# rail_safety.net
KiCad netlist of a schematic drawn in Altium Designer
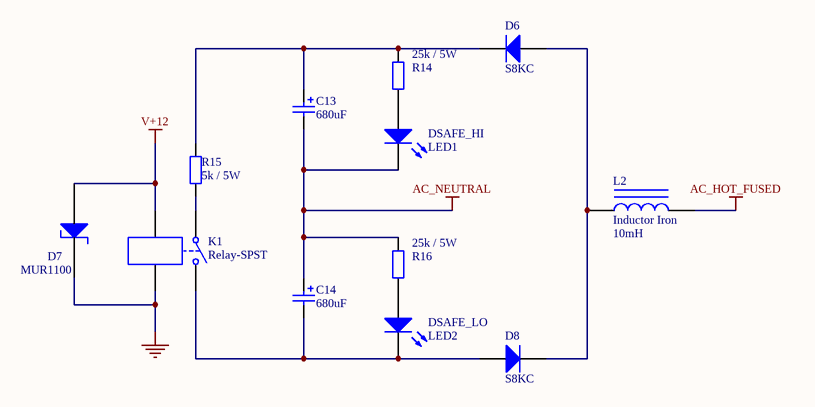
[diagram p0: rail_safety.SchDoc]

(export (version "E")
  (design (tool "Eeschema 10.0.6"))
  (components
    (comp (ref "C13")
      (value "680uF")
      (footprint "Cap_450v_680uF")
      (description "Polarized Capacitor (Surface Mount)")
      (fields (field (name "Comment") "Cap Pol3") (field (name "PUBLISHER") "Altium Limited"))
      (libsource (lib "Miscellaneous Devices") (part "Cap Pol3"))
    )
    (comp (ref "C14")
      (value "680uF")
      (footprint "Cap_450v_680uF")
      (description "Polarized Capacitor (Surface Mount)")
      (fields (field (name "Comment") "Cap Pol3") (field (name "PUBLISHER") "Altium Limited"))
      (libsource (lib "Miscellaneous Devices") (part "Cap Pol3"))
    )
    (comp (ref "D6")
      (value "S8KC")
      (description "3 Amp Medium Power Silicon Rectifier Diode")
      (fields (field (name "PUBLISHER") "Altium Limited"))
      (libsource (lib "Miscellaneous Devices") (part "Diode 1N5408"))
    )
    (comp (ref "D7")
      (value "MUR1100")
      (footprint "DIODE-0.4")
      (libsource (lib "components") (part "MUR1100"))
    )
    (comp (ref "D8")
      (value "S8KC")
      (footprint "DIO18.84-9.6x5.6")
      (description "3 Amp Medium Power Silicon Rectifier Diode")
      (fields (field (name "PUBLISHER") "Altium Limited"))
      (libsource (lib "Miscellaneous Devices") (part "Diode 1N5408"))
    )
    (comp (ref "DSAFE_HI")
      (value "LED1")
      (footprint "CAPC1608N")
      (description "Typical BLUE SiC LED")
      (fields (field (name "PUBLISHER") "Altium Limited"))
      (libsource (lib "Miscellaneous Devices") (part "LED3"))
    )
    (comp (ref "DSAFE_LO")
      (value "LED2")
      (footprint "CAPC1608N")
      (description "Typical BLUE SiC LED")
      (fields (field (name "PUBLISHER") "Altium Limited"))
      (libsource (lib "Miscellaneous Devices") (part "LED3"))
    )
    (comp (ref "K1")
      (value "Relay-SPST")
      (footprint "SRD-05VDC-SL-A")
      (description "Single-Pole Single-Throw Relay")
      (fields (field (name "PUBLISHER") "Altium Limited"))
      (libsource (lib "Miscellaneous Devices") (part "Relay-SPST"))
    )
    (comp (ref "L2")
      (value "Inductor Iron")
      (footprint "BigInductor")
      (description "Magnetic-Core Inductor")
      (fields (field (name "ALTIUM_VALUE") "10mH") (field (name "PUBLISHER") "Altium Limited"))
      (libsource (lib "Miscellaneous Devices") (part "Inductor Iron"))
    )
    (comp (ref "R14")
      (value "25k / 5W")
      (footprint "AXIAL-1.0")
      (description "Resistor")
      (fields (field (name "PUBLISHER") "Altium Limited"))
      (libsource (lib "*") (part "Res2"))
    )
    (comp (ref "R15")
      (value "5k / 5W")
      (footprint "AXIAL-1.0")
      (description "Resistor")
      (fields (field (name "PUBLISHER") "Altium Limited"))
      (libsource (lib "") (part "Res2_1"))
    )
    (comp (ref "R16")
      (value "25k / 5W")
      (footprint "AXIAL-1.0")
      (description "Resistor")
      (fields (field (name "PUBLISHER") "Altium Limited"))
      (libsource (lib "*") (part "Res2"))
    )
  )
  (nets
    (net (code "1") (name "AC_HOT_FUSED") (class "Default")
      (node (ref "L2") (pin "2") (pinfunction "2_2") (pintype "passive"))
    )
    (net (code "2") (name "AC_NEUTRAL") (class "Default")
      (node (ref "C13") (pin "2") (pinfunction "2_2") (pintype "passive"))
      (node (ref "C14") (pin "1") (pinfunction "1_1") (pintype "passive"))
      (node (ref "DSAFE_HI") (pin "2") (pinfunction "K_2") (pintype "passive"))
      (node (ref "R16") (pin "2") (pinfunction "2_2") (pintype "passive"))
    )
    (net (code "3") (name "GND") (class "Default")
      (node (ref "D7") (pin "2") (pinfunction "2_2") (pintype "passive"))
      (node (ref "K1") (pin "4") (pinfunction "4_4") (pintype "passive"))
    )
    (net (code "4") (name "Net-(D6-A)") (class "Default")
      (node (ref "D6") (pin "1") (pinfunction "A_1") (pintype "passive"))
      (node (ref "D8") (pin "2") (pinfunction "K_2") (pintype "passive"))
      (node (ref "L2") (pin "1") (pinfunction "1_1") (pintype "passive"))
    )
    (net (code "5") (name "Net-(D6-K)") (class "Default")
      (node (ref "C13") (pin "1") (pinfunction "1_1") (pintype "passive"))
      (node (ref "D6") (pin "2") (pinfunction "K_2") (pintype "passive"))
      (node (ref "R14") (pin "2") (pinfunction "2_2") (pintype "passive"))
      (node (ref "R15") (pin "1") (pinfunction "1_1") (pintype "passive"))
    )
    (net (code "6") (name "Net-(D8-A)") (class "Default")
      (node (ref "C14") (pin "2") (pinfunction "2_2") (pintype "passive"))
      (node (ref "D8") (pin "1") (pinfunction "A_1") (pintype "passive"))
      (node (ref "DSAFE_LO") (pin "2") (pinfunction "K_2") (pintype "passive"))
      (node (ref "K1") (pin "2") (pinfunction "2_2") (pintype "passive"))
    )
    (net (code "7") (name "Net-(DSAFE_HI-A)") (class "Default")
      (node (ref "DSAFE_HI") (pin "1") (pinfunction "A_1") (pintype "passive"))
      (node (ref "R14") (pin "1") (pinfunction "1_1") (pintype "passive"))
    )
    (net (code "8") (name "Net-(DSAFE_LO-A)") (class "Default")
      (node (ref "DSAFE_LO") (pin "1") (pinfunction "A_1") (pintype "passive"))
      (node (ref "R16") (pin "1") (pinfunction "1_1") (pintype "passive"))
    )
    (net (code "9") (name "Net-(K1-Pad1)") (class "Default")
      (node (ref "K1") (pin "1") (pinfunction "1_1") (pintype "passive"))
      (node (ref "R15") (pin "2") (pinfunction "2_2") (pintype "passive"))
    )
    (net (code "10") (name "V+12") (class "Default")
      (node (ref "D7") (pin "1") (pinfunction "1_1") (pintype "passive"))
      (node (ref "K1") (pin "3") (pinfunction "3_3") (pintype "passive"))
    )
  )
)
